# Vocm_Gen.net
KiCad netlist of a schematic drawn in Altium Designer
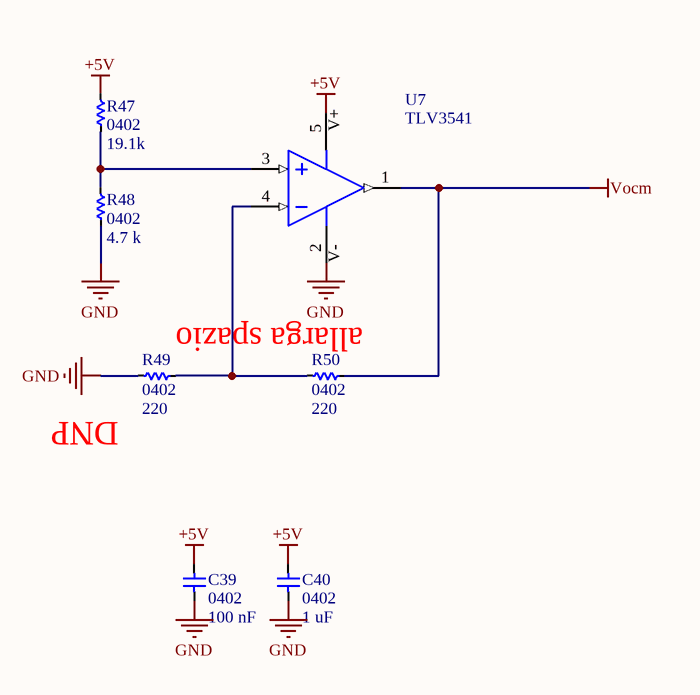
[diagram p0: Vocm_Gen.SchDoc]

(export (version "E")
  (design (tool "Eeschema 10.0.6"))
  (components
    (comp (ref "C39")
      (value "0402")
      (footprint "CAPCERSMD0402")
      (fields (field (name "ALTIUM_VALUE") "100 nF"))
      (libsource (lib "0402_Cap_Cer__SARAversion-23") (part "CAPCER0402_X7R_50V_100n"))
    )
    (comp (ref "C40")
      (value "0402")
      (footprint "CAPCERSMD0402")
      (fields (field (name "ALTIUM_VALUE") "1 uF"))
      (libsource (lib "0402_Cap_Cer__SARAversion-23") (part "CAPCER0402_X5R_10V_1u"))
    )
    (comp (ref "R47")
      (value "0402")
      (footprint "RESSMD0402")
      (fields (field (name "ALTIUM_VALUE") "19.1k"))
      (libsource (lib "0402_Resistors__SARAversion-52") (part "RES0402-19k1"))
    )
    (comp (ref "R48")
      (value "0402")
      (footprint "RESSMD0402")
      (fields (field (name "ALTIUM_VALUE") "4.7 k"))
      (libsource (lib "0402_Resistors__SARAversion-52") (part "RES0402-4k7"))
    )
    (comp (ref "R49")
      (value "0402")
      (footprint "RESSMD0402")
      (fields (field (name "ALTIUM_VALUE") "220"))
      (libsource (lib "0402_Resistors__SARAversion-52") (part "RES0402-220R"))
    )
    (comp (ref "R50")
      (value "0402")
      (footprint "RESSMD0402")
      (fields (field (name "ALTIUM_VALUE") "220"))
      (libsource (lib "0402_Resistors__SARAversion-52") (part "RES0402-220R"))
    )
    (comp (ref "U7")
      (value "TLV3541")
      (footprint "SOT5_P95W280L290H145")
      (description "TLV3541 200-MHz, Rail-to-Rail OPAMP")
      (libsource (lib "OPAMPs__SARAversion-54") (part "TLV3541IDBVT"))
    )
  )
  (nets
    (net (code "1") (name "+5V") (class "Default")
      (node (ref "C39") (pin "2") (pinfunction "2_2") (pintype "passive"))
      (node (ref "C40") (pin "2") (pinfunction "2_2") (pintype "passive"))
      (node (ref "R47") (pin "1") (pinfunction "1_1") (pintype "passive"))
      (node (ref "U7") (pin "5") (pinfunction "V+_5") (pintype "power_in"))
    )
    (net (code "2") (name "GND") (class "Default")
      (node (ref "C39") (pin "1") (pinfunction "1_1") (pintype "passive"))
      (node (ref "C40") (pin "1") (pinfunction "1_1") (pintype "passive"))
      (node (ref "R48") (pin "2") (pinfunction "2_2") (pintype "passive"))
      (node (ref "R49") (pin "1") (pinfunction "1_1") (pintype "passive"))
      (node (ref "U7") (pin "2") (pinfunction "V-_2") (pintype "power_in"))
    )
    (net (code "3") (name "Net-(U7-IN+)") (class "Default")
      (node (ref "R47") (pin "2") (pinfunction "2_2") (pintype "passive"))
      (node (ref "R48") (pin "1") (pinfunction "1_1") (pintype "passive"))
      (node (ref "U7") (pin "3") (pinfunction "IN+_3") (pintype "input"))
    )
    (net (code "4") (name "Net-(U7-IN-)") (class "Default")
      (node (ref "R49") (pin "2") (pinfunction "2_2") (pintype "passive"))
      (node (ref "R50") (pin "1") (pinfunction "1_1") (pintype "passive"))
      (node (ref "U7") (pin "4") (pinfunction "IN-_4") (pintype "input"))
    )
    (net (code "5") (name "Vocm") (class "Default")
      (node (ref "R50") (pin "2") (pinfunction "2_2") (pintype "passive"))
      (node (ref "U7") (pin "1") (pinfunction "OUT_1") (pintype "output"))
    )
  )
)
